# LeftHandPath.net
KiCad netlist of a schematic drawn in EAGLE
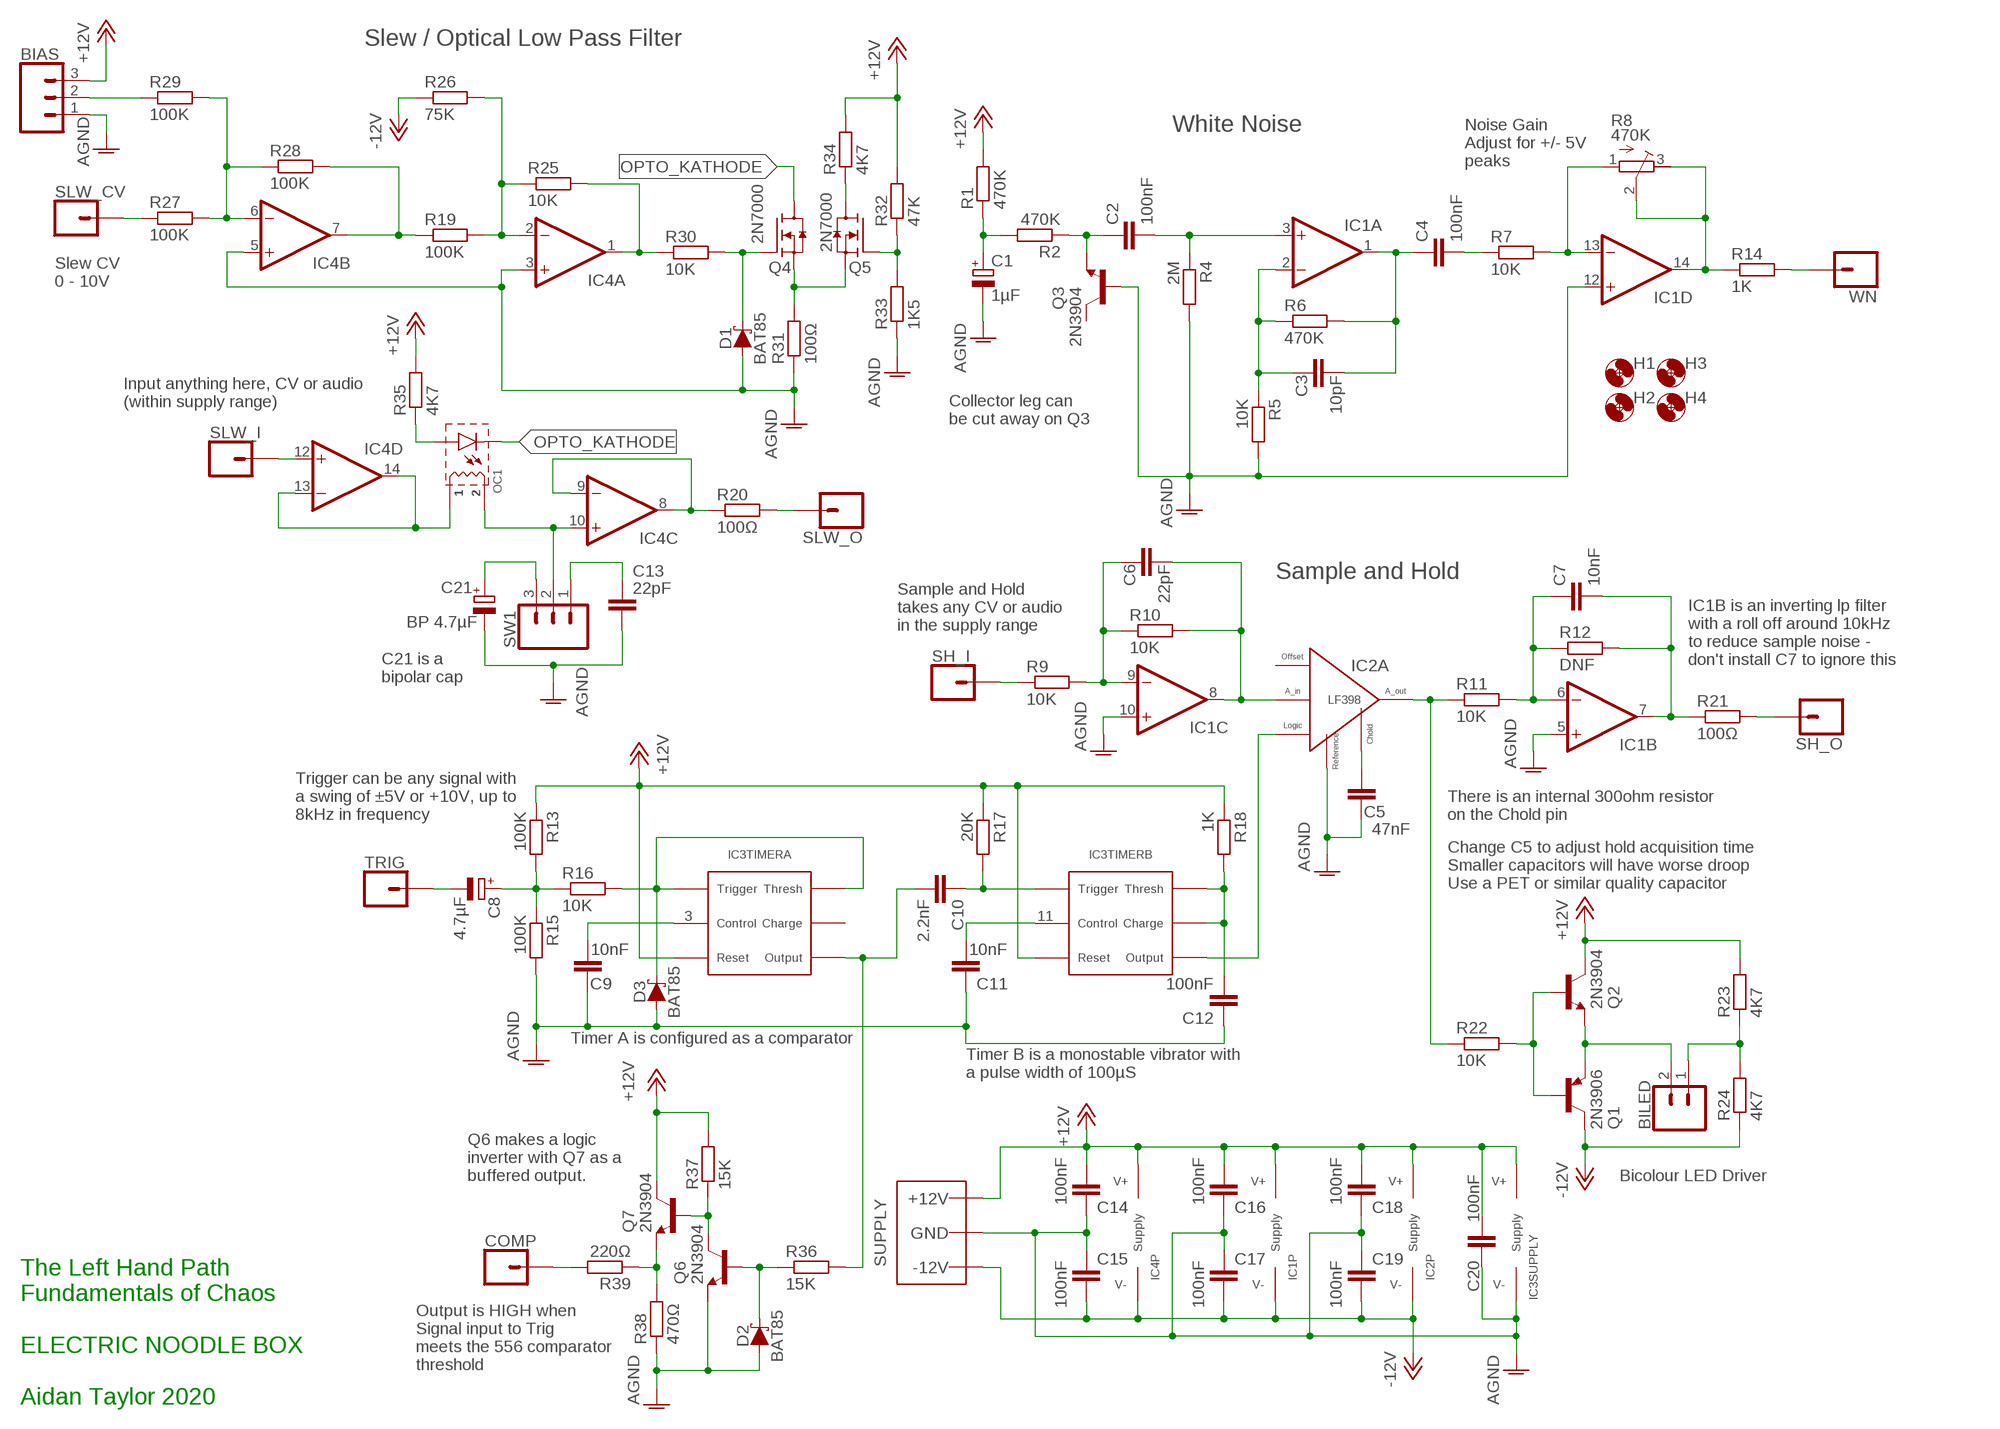
[diagram p0: schematic, sheet 1]

(export (version "E")
  (design (tool "Eeschema 10.0.6"))
  (components
    (comp (ref "BIAS")
      (value "3XWIREPAD")
      (footprint "eagle-import:1X03")
      (libsource (lib "eagle-import") (part "3XWIREPAD"))
    )
    (comp (ref "BILED")
      (value "2XWIREPAD")
      (footprint "eagle-import:1X02")
      (libsource (lib "eagle-import") (part "2XWIREPAD"))
    )
    (comp (ref "C1")
      (value "1µF")
      (footprint "eagle-import:E2-5")
      (libsource (lib "eagle-import") (part "CPOL-EUE2-5"))
    )
    (comp (ref "C2")
      (value "100nF")
      (footprint "eagle-import:C050-025X075")
      (libsource (lib "eagle-import") (part "C-EU050-025X075"))
    )
    (comp (ref "C3")
      (value "10pF")
      (footprint "eagle-import:C050-025X075")
      (libsource (lib "eagle-import") (part "C-EU050-025X075"))
    )
    (comp (ref "C4")
      (value "100nF")
      (footprint "eagle-import:C050-025X075")
      (libsource (lib "eagle-import") (part "C-EU050-025X075"))
    )
    (comp (ref "C5")
      (value "47nF")
      (footprint "eagle-import:C050-025X075")
      (libsource (lib "eagle-import") (part "C-EU050-025X075"))
    )
    (comp (ref "C6")
      (value "22pF")
      (footprint "eagle-import:C050-025X075")
      (libsource (lib "eagle-import") (part "C-EU050-025X075"))
    )
    (comp (ref "C7")
      (value "10nF")
      (footprint "eagle-import:C050-025X075")
      (libsource (lib "eagle-import") (part "C-EU050-025X075"))
    )
    (comp (ref "C8")
      (value "4.7µF")
      (footprint "eagle-import:E2-5")
      (libsource (lib "eagle-import") (part "CPOL-EUE2-5"))
    )
    (comp (ref "C9")
      (value "10nF")
      (footprint "eagle-import:C050-025X075")
      (libsource (lib "eagle-import") (part "C-EU050-025X075"))
    )
    (comp (ref "C10")
      (value "2.2nF")
      (footprint "eagle-import:C050-025X075")
      (libsource (lib "eagle-import") (part "C-EU050-025X075"))
    )
    (comp (ref "C11")
      (value "10nF")
      (footprint "eagle-import:C050-025X075")
      (libsource (lib "eagle-import") (part "C-EU050-025X075"))
    )
    (comp (ref "C12")
      (value "100nF")
      (footprint "eagle-import:C050-025X075")
      (libsource (lib "eagle-import") (part "C-EU050-025X075"))
    )
    (comp (ref "C13")
      (value "22pF")
      (footprint "eagle-import:C050-025X075")
      (libsource (lib "eagle-import") (part "C-EU050-025X075"))
    )
    (comp (ref "C14")
      (value "100nF")
      (footprint "eagle-import:C050-025X075")
      (libsource (lib "eagle-import") (part "C-EU050-025X075"))
    )
    (comp (ref "C15")
      (value "100nF")
      (footprint "eagle-import:C050-025X075")
      (libsource (lib "eagle-import") (part "C-EU050-025X075"))
    )
    (comp (ref "C16")
      (value "100nF")
      (footprint "eagle-import:C050-025X075")
      (libsource (lib "eagle-import") (part "C-EU050-025X075"))
    )
    (comp (ref "C17")
      (value "100nF")
      (footprint "eagle-import:C050-025X075")
      (libsource (lib "eagle-import") (part "C-EU050-025X075"))
    )
    (comp (ref "C18")
      (value "100nF")
      (footprint "eagle-import:C050-025X075")
      (libsource (lib "eagle-import") (part "C-EU050-025X075"))
    )
    (comp (ref "C19")
      (value "100nF")
      (footprint "eagle-import:C050-025X075")
      (libsource (lib "eagle-import") (part "C-EU050-025X075"))
    )
    (comp (ref "C20")
      (value "100nF")
      (footprint "eagle-import:C050-025X075")
      (libsource (lib "eagle-import") (part "C-EU050-025X075"))
    )
    (comp (ref "C21")
      (value "BP 4.7µF")
      (footprint "eagle-import:E2-5")
      (libsource (lib "eagle-import") (part "CPOL-EUE2-5"))
    )
    (comp (ref "COMP")
      (value "1XWIREPAD")
      (footprint "eagle-import:1X01")
      (libsource (lib "eagle-import") (part "1XWIREPAD"))
    )
    (comp (ref "D1")
      (value "BAT85")
      (footprint "eagle-import:DO35-7")
      (libsource (lib "eagle-import") (part "SCHOTTKY_DO35"))
    )
    (comp (ref "D2")
      (value "BAT85")
      (footprint "eagle-import:DO35-7")
      (libsource (lib "eagle-import") (part "SCHOTTKY_DO35"))
    )
    (comp (ref "D3")
      (value "BAT85")
      (footprint "eagle-import:DO35-7")
      (libsource (lib "eagle-import") (part "SCHOTTKY_DO35"))
    )
    (comp (ref "H1")
      (value "MOUNT-HOLE3.2")
      (footprint "eagle-import:3,2")
      (libsource (lib "eagle-import") (part "MOUNT-HOLE3.2"))
    )
    (comp (ref "H2")
      (value "MOUNT-HOLE3.2")
      (footprint "eagle-import:3,2")
      (libsource (lib "eagle-import") (part "MOUNT-HOLE3.2"))
    )
    (comp (ref "H3")
      (value "MOUNT-HOLE3.2")
      (footprint "eagle-import:3,2")
      (libsource (lib "eagle-import") (part "MOUNT-HOLE3.2"))
    )
    (comp (ref "H4")
      (value "MOUNT-HOLE3.2")
      (footprint "eagle-import:3,2")
      (libsource (lib "eagle-import") (part "MOUNT-HOLE3.2"))
    )
    (comp (ref "IC1")
      (value "TL0X4DIL")
      (footprint "eagle-import:DIL14")
      (libsource (lib "eagle-import") (part "TL0X4DIL"))
    )
    (comp (ref "IC2")
      (value "LF398")
      (footprint "eagle-import:DIL08")
      (libsource (lib "eagle-import") (part "LF398"))
    )
    (comp (ref "IC3")
      (value "556_DUALTIMERDIL14")
      (footprint "eagle-import:DIL14")
      (libsource (lib "eagle-import") (part "556_DUALTIMERDIL14"))
    )
    (comp (ref "IC4")
      (value "TL0X4DIL")
      (footprint "eagle-import:DIL14")
      (libsource (lib "eagle-import") (part "TL0X4DIL"))
    )
    (comp (ref "OC1")
      (value "OPTOCOUPLERSILONEX")
      (footprint "eagle-import:SILONEX_OPTOCOUPLER")
      (libsource (lib "eagle-import") (part "OPTOCOUPLERSILONEX"))
    )
    (comp (ref "Q1")
      (value "2N3906")
      (footprint "eagle-import:TO92")
      (libsource (lib "eagle-import") (part "2N3906"))
    )
    (comp (ref "Q2")
      (value "2N3904")
      (footprint "eagle-import:TO92")
      (libsource (lib "eagle-import") (part "2N3904"))
    )
    (comp (ref "Q3")
      (value "2N3904")
      (footprint "eagle-import:TO92")
      (libsource (lib "eagle-import") (part "2N3904"))
    )
    (comp (ref "Q4")
      (value "2N7000")
      (footprint "eagle-import:TO92")
      (libsource (lib "eagle-import") (part "2N7000"))
    )
    (comp (ref "Q5")
      (value "2N7000")
      (footprint "eagle-import:TO92")
      (libsource (lib "eagle-import") (part "2N7000"))
    )
    (comp (ref "Q6")
      (value "2N3904")
      (footprint "eagle-import:TO92")
      (libsource (lib "eagle-import") (part "2N3904"))
    )
    (comp (ref "Q7")
      (value "2N3904")
      (footprint "eagle-import:TO92")
      (libsource (lib "eagle-import") (part "2N3904"))
    )
    (comp (ref "R1")
      (value "470K")
      (footprint "eagle-import:0207_7")
      (libsource (lib "eagle-import") (part "R-EU_0207/7"))
    )
    (comp (ref "R2")
      (value "470K")
      (footprint "eagle-import:0207_7")
      (libsource (lib "eagle-import") (part "R-EU_0207/7"))
    )
    (comp (ref "R4")
      (value "2M")
      (footprint "eagle-import:0207_7")
      (libsource (lib "eagle-import") (part "R-EU_0207/7"))
    )
    (comp (ref "R5")
      (value "10K")
      (footprint "eagle-import:0207_7")
      (libsource (lib "eagle-import") (part "R-EU_0207/7"))
    )
    (comp (ref "R6")
      (value "470K")
      (footprint "eagle-import:0207_7")
      (libsource (lib "eagle-import") (part "R-EU_0207/7"))
    )
    (comp (ref "R7")
      (value "10K")
      (footprint "eagle-import:0207_7")
      (libsource (lib "eagle-import") (part "R-EU_0207/7"))
    )
    (comp (ref "R8")
      (value "470K")
      (footprint "eagle-import:RTRIM3296W")
      (libsource (lib "eagle-import") (part "R-TRIMM3296W"))
    )
    (comp (ref "R9")
      (value "10K")
      (footprint "eagle-import:0207_7")
      (libsource (lib "eagle-import") (part "R-EU_0207/7"))
    )
    (comp (ref "R10")
      (value "10K")
      (footprint "eagle-import:0207_7")
      (libsource (lib "eagle-import") (part "R-EU_0207/7"))
    )
    (comp (ref "R11")
      (value "10K")
      (footprint "eagle-import:0207_7")
      (libsource (lib "eagle-import") (part "R-EU_0207/7"))
    )
    (comp (ref "R12")
      (value "DNF")
      (footprint "eagle-import:0207_7")
      (libsource (lib "eagle-import") (part "R-EU_0207/7"))
    )
    (comp (ref "R13")
      (value "100K")
      (footprint "eagle-import:0207_7")
      (libsource (lib "eagle-import") (part "R-EU_0207/7"))
    )
    (comp (ref "R14")
      (value "1K")
      (footprint "eagle-import:0207_7")
      (libsource (lib "eagle-import") (part "R-EU_0207/7"))
    )
    (comp (ref "R15")
      (value "100K")
      (footprint "eagle-import:0207_7")
      (libsource (lib "eagle-import") (part "R-EU_0207/7"))
    )
    (comp (ref "R16")
      (value "10K")
      (footprint "eagle-import:0207_7")
      (libsource (lib "eagle-import") (part "R-EU_0207/7"))
    )
    (comp (ref "R17")
      (value "20K")
      (footprint "eagle-import:0207_7")
      (libsource (lib "eagle-import") (part "R-EU_0207/7"))
    )
    (comp (ref "R18")
      (value "1K")
      (footprint "eagle-import:0207_7")
      (libsource (lib "eagle-import") (part "R-EU_0207/7"))
    )
    (comp (ref "R19")
      (value "100K")
      (footprint "eagle-import:0207_7")
      (libsource (lib "eagle-import") (part "R-EU_0207/7"))
    )
    (comp (ref "R20")
      (value "100Ω")
      (footprint "eagle-import:0207_7")
      (libsource (lib "eagle-import") (part "R-EU_0207/7"))
    )
    (comp (ref "R21")
      (value "100Ω")
      (footprint "eagle-import:0207_7")
      (libsource (lib "eagle-import") (part "R-EU_0207/7"))
    )
    (comp (ref "R22")
      (value "10K")
      (footprint "eagle-import:0207_7")
      (libsource (lib "eagle-import") (part "R-EU_0207/7"))
    )
    (comp (ref "R23")
      (value "4K7")
      (footprint "eagle-import:0207_7")
      (libsource (lib "eagle-import") (part "R-EU_0207/7"))
    )
    (comp (ref "R24")
      (value "4K7")
      (footprint "eagle-import:0207_7")
      (libsource (lib "eagle-import") (part "R-EU_0207/7"))
    )
    (comp (ref "R25")
      (value "10K")
      (footprint "eagle-import:0207_7")
      (libsource (lib "eagle-import") (part "R-EU_0207/7"))
    )
    (comp (ref "R26")
      (value "75K")
      (footprint "eagle-import:0207_7")
      (libsource (lib "eagle-import") (part "R-EU_0207/7"))
    )
    (comp (ref "R27")
      (value "100K")
      (footprint "eagle-import:0207_7")
      (libsource (lib "eagle-import") (part "R-EU_0207/7"))
    )
    (comp (ref "R28")
      (value "100K")
      (footprint "eagle-import:0207_7")
      (libsource (lib "eagle-import") (part "R-EU_0207/7"))
    )
    (comp (ref "R29")
      (value "100K")
      (footprint "eagle-import:0207_7")
      (libsource (lib "eagle-import") (part "R-EU_0207/7"))
    )
    (comp (ref "R30")
      (value "10K")
      (footprint "eagle-import:0207_7")
      (libsource (lib "eagle-import") (part "R-EU_0207/7"))
    )
    (comp (ref "R31")
      (value "100Ω")
      (footprint "eagle-import:0207_7")
      (libsource (lib "eagle-import") (part "R-EU_0207/7"))
    )
    (comp (ref "R32")
      (value "47K")
      (footprint "eagle-import:0207_7")
      (libsource (lib "eagle-import") (part "R-EU_0207/7"))
    )
    (comp (ref "R33")
      (value "1K5")
      (footprint "eagle-import:0207_7")
      (libsource (lib "eagle-import") (part "R-EU_0207/7"))
    )
    (comp (ref "R34")
      (value "4K7")
      (footprint "eagle-import:0207_7")
      (libsource (lib "eagle-import") (part "R-EU_0207/7"))
    )
    (comp (ref "R35")
      (value "4K7")
      (footprint "eagle-import:0207_7")
      (libsource (lib "eagle-import") (part "R-EU_0207/7"))
    )
    (comp (ref "R36")
      (value "15K")
      (footprint "eagle-import:0207_7")
      (libsource (lib "eagle-import") (part "R-EU_0207/7"))
    )
    (comp (ref "R37")
      (value "15K")
      (footprint "eagle-import:0207_7")
      (libsource (lib "eagle-import") (part "R-EU_0207/7"))
    )
    (comp (ref "R38")
      (value "470Ω")
      (footprint "eagle-import:0207_7")
      (libsource (lib "eagle-import") (part "R-EU_0207/7"))
    )
    (comp (ref "R39")
      (value "220Ω")
      (footprint "eagle-import:0207_7")
      (libsource (lib "eagle-import") (part "R-EU_0207/7"))
    )
    (comp (ref "SH_I")
      (value "1XWIREPAD")
      (footprint "eagle-import:1X01")
      (libsource (lib "eagle-import") (part "1XWIREPAD"))
    )
    (comp (ref "SH_O")
      (value "1XWIREPAD")
      (footprint "eagle-import:1X01")
      (libsource (lib "eagle-import") (part "1XWIREPAD"))
    )
    (comp (ref "SLW_CV")
      (value "1XWIREPAD")
      (footprint "eagle-import:1X01")
      (libsource (lib "eagle-import") (part "1XWIREPAD"))
    )
    (comp (ref "SLW_I")
      (value "1XWIREPAD")
      (footprint "eagle-import:1X01")
      (libsource (lib "eagle-import") (part "1XWIREPAD"))
    )
    (comp (ref "SLW_O")
      (value "1XWIREPAD")
      (footprint "eagle-import:1X01")
      (libsource (lib "eagle-import") (part "1XWIREPAD"))
    )
    (comp (ref "SW1")
      (value "3XWIREPAD")
      (footprint "eagle-import:1X03")
      (libsource (lib "eagle-import") (part "3XWIREPAD"))
    )
    (comp (ref "TRIG")
      (value "1XWIREPAD")
      (footprint "eagle-import:1X01")
      (libsource (lib "eagle-import") (part "1XWIREPAD"))
    )
    (comp (ref "WN")
      (value "1XWIREPAD")
      (footprint "eagle-import:1X01")
      (libsource (lib "eagle-import") (part "1XWIREPAD"))
    )
    (comp (ref "WP1")
      (value "COMBO_SUPPLY_HEADER")
      (footprint "eagle-import:COMBINED_POWER")
      (libsource (lib "eagle-import") (part "COMBO_SUPPLY_HEADER"))
    )
  )
  (nets
    (net (code "1") (name "+12V") (class "Default")
      (node (ref "BIAS") (pin "3") (pinfunction "3_3") (pintype "passive"))
      (node (ref "C14") (pin "2") (pinfunction "2_2") (pintype "passive"))
      (node (ref "C16") (pin "2") (pinfunction "2_2") (pintype "passive"))
      (node (ref "C18") (pin "2") (pinfunction "2_2") (pintype "passive"))
      (node (ref "C20") (pin "2") (pinfunction "2_2") (pintype "passive"))
      (node (ref "IC1") (pin "4") (pinfunction "V+_4") (pintype "bidirectional"))
      (node (ref "IC2") (pin "1") (pinfunction "V+_1") (pintype "bidirectional"))
      (node (ref "IC3") (pin "10") (pinfunction "RESET_10") (pintype "bidirectional"))
      (node (ref "IC3") (pin "14") (pinfunction "V+_14") (pintype "bidirectional"))
      (node (ref "IC3") (pin "4") (pinfunction "RESET_4") (pintype "bidirectional"))
      (node (ref "IC4") (pin "4") (pinfunction "V+_4") (pintype "bidirectional"))
      (node (ref "Q2") (pin "1") (pinfunction "C_1") (pintype "passive"))
      (node (ref "Q7") (pin "1") (pinfunction "C_1") (pintype "passive"))
      (node (ref "R1") (pin "2") (pinfunction "2_2") (pintype "passive"))
      (node (ref "R13") (pin "1") (pinfunction "1_1") (pintype "passive"))
      (node (ref "R17") (pin "1") (pinfunction "1_1") (pintype "passive"))
      (node (ref "R18") (pin "1") (pinfunction "1_1") (pintype "passive"))
      (node (ref "R23") (pin "2") (pinfunction "2_2") (pintype "passive"))
      (node (ref "R32") (pin "2") (pinfunction "2_2") (pintype "passive"))
      (node (ref "R34") (pin "2") (pinfunction "2_2") (pintype "passive"))
      (node (ref "R35") (pin "2") (pinfunction "2_2") (pintype "passive"))
      (node (ref "R37") (pin "2") (pinfunction "2_2") (pintype "passive"))
      (node (ref "WP1") (pin "V+1") (pinfunction "V++_V+1") (pintype "power_in"))
      (node (ref "WP1") (pin "V+2") (pinfunction "V++_V+2") (pintype "power_in"))
      (node (ref "WP1") (pin "V+3") (pinfunction "V++_V+3") (pintype "power_in"))
    )
    (net (code "2") (name "-12V") (class "Default")
      (node (ref "C15") (pin "1") (pinfunction "1_1") (pintype "passive"))
      (node (ref "C17") (pin "1") (pinfunction "1_1") (pintype "passive"))
      (node (ref "C19") (pin "1") (pinfunction "1_1") (pintype "passive"))
      (node (ref "IC1") (pin "11") (pinfunction "V-_11") (pintype "bidirectional"))
      (node (ref "IC2") (pin "4") (pinfunction "V-_4") (pintype "bidirectional"))
      (node (ref "IC4") (pin "11") (pinfunction "V-_11") (pintype "bidirectional"))
      (node (ref "Q1") (pin "1") (pinfunction "C_1") (pintype "passive"))
      (node (ref "R24") (pin "1") (pinfunction "1_1") (pintype "passive"))
      (node (ref "R26") (pin "1") (pinfunction "1_1") (pintype "passive"))
      (node (ref "WP1") (pin "V-1") (pinfunction "V--_V-1") (pintype "power_in"))
      (node (ref "WP1") (pin "V-2") (pinfunction "V--_V-2") (pintype "power_in"))
      (node (ref "WP1") (pin "V-3") (pinfunction "V--_V-3") (pintype "power_in"))
    )
    (net (code "3") (name "AGND") (class "Default")
      (node (ref "BIAS") (pin "1") (pinfunction "1_1") (pintype "passive"))
      (node (ref "C1") (pin "-") (pinfunction "-_-") (pintype "passive"))
      (node (ref "C11") (pin "1") (pinfunction "1_1") (pintype "passive"))
      (node (ref "C12") (pin "1") (pinfunction "1_1") (pintype "passive"))
      (node (ref "C13") (pin "1") (pinfunction "1_1") (pintype "passive"))
      (node (ref "C14") (pin "1") (pinfunction "1_1") (pintype "passive"))
      (node (ref "C15") (pin "2") (pinfunction "2_2") (pintype "passive"))
      (node (ref "C16") (pin "1") (pinfunction "1_1") (pintype "passive"))
      (node (ref "C17") (pin "2") (pinfunction "2_2") (pintype "passive"))
      (node (ref "C18") (pin "1") (pinfunction "1_1") (pintype "passive"))
      (node (ref "C19") (pin "2") (pinfunction "2_2") (pintype "passive"))
      (node (ref "C20") (pin "1") (pinfunction "1_1") (pintype "passive"))
      (node (ref "C21") (pin "-") (pinfunction "-_-") (pintype "passive"))
      (node (ref "C5") (pin "1") (pinfunction "1_1") (pintype "passive"))
      (node (ref "C9") (pin "1") (pinfunction "1_1") (pintype "passive"))
      (node (ref "D1") (pin "A") (pinfunction "A_A") (pintype "passive"))
      (node (ref "D2") (pin "A") (pinfunction "A_A") (pintype "passive"))
      (node (ref "D3") (pin "A") (pinfunction "A_A") (pintype "passive"))
      (node (ref "IC1") (pin "10") (pinfunction "+IN_10") (pintype "input"))
      (node (ref "IC1") (pin "12") (pinfunction "+IN_12") (pintype "input"))
      (node (ref "IC1") (pin "5") (pinfunction "+IN_5") (pintype "input"))
      (node (ref "IC2") (pin "7") (pinfunction "REFERENCE_7") (pintype "input"))
      (node (ref "IC3") (pin "7") (pinfunction "V-_7") (pintype "bidirectional"))
      (node (ref "IC4") (pin "3") (pinfunction "+IN_3") (pintype "input"))
      (node (ref "IC4") (pin "5") (pinfunction "+IN_5") (pintype "input"))
      (node (ref "Q3") (pin "2") (pinfunction "B_2") (pintype "passive"))
      (node (ref "Q6") (pin "3") (pinfunction "E_3") (pintype "passive"))
      (node (ref "R15") (pin "2") (pinfunction "2_2") (pintype "passive"))
      (node (ref "R31") (pin "1") (pinfunction "1_1") (pintype "passive"))
      (node (ref "R33") (pin "1") (pinfunction "1_1") (pintype "passive"))
      (node (ref "R38") (pin "1") (pinfunction "1_1") (pintype "passive"))
      (node (ref "R4") (pin "2") (pinfunction "2_2") (pintype "passive"))
      (node (ref "R5") (pin "2") (pinfunction "2_2") (pintype "passive"))
      (node (ref "WP1") (pin "GND1") (pinfunction "AGND_GND1") (pintype "power_in"))
      (node (ref "WP1") (pin "GND2") (pinfunction "AGND_GND2") (pintype "power_in"))
      (node (ref "WP1") (pin "GND3") (pinfunction "AGND_GND3") (pintype "power_in"))
      (node (ref "WP1") (pin "GND4") (pinfunction "AGND_GND4") (pintype "power_in"))
      (node (ref "WP1") (pin "GND5") (pinfunction "AGND_GND5") (pintype "power_in"))
      (node (ref "WP1") (pin "GND6") (pinfunction "AGND_GND6") (pintype "power_in"))
      (node (ref "WP1") (pin "GND7") (pinfunction "AGND_GND7") (pintype "power_in"))
      (node (ref "WP1") (pin "GND8") (pinfunction "AGND_GND8") (pintype "power_in"))
    )
    (net (code "4") (name "Net-(BIAS-Pad2)") (class "Default")
      (node (ref "BIAS") (pin "2") (pinfunction "2_2") (pintype "passive"))
      (node (ref "R29") (pin "1") (pinfunction "1_1") (pintype "passive"))
    )
    (net (code "5") (name "Net-(BILED-Pad1)") (class "Default")
      (node (ref "BILED") (pin "1") (pinfunction "1_1") (pintype "passive"))
      (node (ref "R23") (pin "1") (pinfunction "1_1") (pintype "passive"))
      (node (ref "R24") (pin "2") (pinfunction "2_2") (pintype "passive"))
    )
    (net (code "6") (name "Net-(C1-Pad+)") (class "Default")
      (node (ref "C1") (pin "+") (pinfunction "+_+") (pintype "passive"))
      (node (ref "R1") (pin "1") (pinfunction "1_1") (pintype "passive"))
      (node (ref "R2") (pin "2") (pinfunction "2_2") (pintype "passive"))
    )
    (net (code "7") (name "Net-(C4-Pad2)") (class "Default")
      (node (ref "C4") (pin "2") (pinfunction "2_2") (pintype "passive"))
      (node (ref "R7") (pin "1") (pinfunction "1_1") (pintype "passive"))
    )
    (net (code "8") (name "Net-(C8-Pad+)") (class "Default")
      (node (ref "C8") (pin "+") (pinfunction "+_+") (pintype "passive"))
      (node (ref "R13") (pin "2") (pinfunction "2_2") (pintype "passive"))
      (node (ref "R15") (pin "1") (pinfunction "1_1") (pintype "passive"))
      (node (ref "R16") (pin "1") (pinfunction "1_1") (pintype "passive"))
    )
    (net (code "9") (name "Net-(C8-Pad-)") (class "Default")
      (node (ref "C8") (pin "-") (pinfunction "-_-") (pintype "passive"))
      (node (ref "TRIG") (pin "1") (pinfunction "1_1") (pintype "passive"))
    )
    (net (code "10") (name "Net-(C13-Pad2)") (class "Default")
      (node (ref "C13") (pin "2") (pinfunction "2_2") (pintype "passive"))
      (node (ref "SW1") (pin "1") (pinfunction "1_1") (pintype "passive"))
    )
    (net (code "11") (name "Net-(C21-Pad+)") (class "Default")
      (node (ref "C21") (pin "+") (pinfunction "+_+") (pintype "passive"))
      (node (ref "SW1") (pin "3") (pinfunction "3_3") (pintype "passive"))
    )
    (net (code "12") (name "Net-(COMP-Pad1)") (class "Default")
      (node (ref "COMP") (pin "1") (pinfunction "1_1") (pintype "passive"))
      (node (ref "R39") (pin "2") (pinfunction "2_2") (pintype "passive"))
    )
    (net (code "13") (name "Net-(IC1A-+IN)") (class "Default")
      (node (ref "C2") (pin "2") (pinfunction "2_2") (pintype "passive"))
      (node (ref "IC1") (pin "3") (pinfunction "+IN_3") (pintype "input"))
      (node (ref "R4") (pin "1") (pinfunction "1_1") (pintype "passive"))
    )
    (net (code "14") (name "Net-(IC1A--IN)") (class "Default")
      (node (ref "C3") (pin "1") (pinfunction "1_1") (pintype "passive"))
      (node (ref "IC1") (pin "2") (pinfunction "-IN_2") (pintype "input"))
      (node (ref "R5") (pin "1") (pinfunction "1_1") (pintype "passive"))
      (node (ref "R6") (pin "1") (pinfunction "1_1") (pintype "passive"))
    )
    (net (code "15") (name "Net-(IC1A-OUT)") (class "Default")
      (node (ref "C3") (pin "2") (pinfunction "2_2") (pintype "passive"))
      (node (ref "C4") (pin "1") (pinfunction "1_1") (pintype "passive"))
      (node (ref "IC1") (pin "1") (pinfunction "OUT_1") (pintype "output"))
      (node (ref "R6") (pin "2") (pinfunction "2_2") (pintype "passive"))
    )
    (net (code "16") (name "Net-(IC1B--IN)") (class "Default")
      (node (ref "C7") (pin "1") (pinfunction "1_1") (pintype "passive"))
      (node (ref "IC1") (pin "6") (pinfunction "-IN_6") (pintype "input"))
      (node (ref "R11") (pin "2") (pinfunction "2_2") (pintype "passive"))
      (node (ref "R12") (pin "1") (pinfunction "1_1") (pintype "passive"))
    )
    (net (code "17") (name "Net-(IC1B-OUT)") (class "Default")
      (node (ref "C7") (pin "2") (pinfunction "2_2") (pintype "passive"))
      (node (ref "IC1") (pin "7") (pinfunction "OUT_7") (pintype "output"))
      (node (ref "R12") (pin "2") (pinfunction "2_2") (pintype "passive"))
      (node (ref "R21") (pin "1") (pinfunction "1_1") (pintype "passive"))
    )
    (net (code "18") (name "Net-(IC1C--IN)") (class "Default")
      (node (ref "C6") (pin "1") (pinfunction "1_1") (pintype "passive"))
      (node (ref "IC1") (pin "9") (pinfunction "-IN_9") (pintype "input"))
      (node (ref "R10") (pin "1") (pinfunction "1_1") (pintype "passive"))
      (node (ref "R9") (pin "2") (pinfunction "2_2") (pintype "passive"))
    )
    (net (code "19") (name "Net-(IC1C-OUT)") (class "Default")
      (node (ref "C6") (pin "2") (pinfunction "2_2") (pintype "passive"))
      (node (ref "IC1") (pin "8") (pinfunction "OUT_8") (pintype "output"))
      (node (ref "IC2") (pin "3") (pinfunction "ANALOG_IN_3") (pintype "input"))
      (node (ref "R10") (pin "2") (pinfunction "2_2") (pintype "passive"))
    )
    (net (code "20") (name "Net-(IC1D--IN)") (class "Default")
      (node (ref "IC1") (pin "13") (pinfunction "-IN_13") (pintype "input"))
      (node (ref "R7") (pin "2") (pinfunction "2_2") (pintype "passive"))
      (node (ref "R8") (pin "1") (pinfunction "A_1") (pintype "passive"))
    )
    (net (code "21") (name "Net-(IC1D-OUT)") (class "Default")
      (node (ref "IC1") (pin "14") (pinfunction "OUT_14") (pintype "output"))
      (node (ref "R14") (pin "1") (pinfunction "1_1") (pintype "passive"))
      (node (ref "R8") (pin "2") (pinfunction "S_2") (pintype "passive"))
      (node (ref "R8") (pin "3") (pinfunction "E_3") (pintype "passive"))
    )
    (net (code "22") (name "Net-(IC2A-ANALOG_OUT)") (class "Default")
      (node (ref "IC2") (pin "5") (pinfunction "ANALOG_OUT_5") (pintype "output"))
      (node (ref "R11") (pin "1") (pinfunction "1_1") (pintype "passive"))
      (node (ref "R22") (pin "1") (pinfunction "1_1") (pintype "passive"))
    )
    (net (code "23") (name "Net-(IC2A-CH)") (class "Default")
      (node (ref "C5") (pin "2") (pinfunction "2_2") (pintype "passive"))
      (node (ref "IC2") (pin "6") (pinfunction "CH_6") (pintype "input"))
    )
    (net (code "24") (name "Net-(IC2A-LOGIC)") (class "Default")
      (node (ref "IC2") (pin "8") (pinfunction "LOGIC_8") (pintype "input"))
      (node (ref "IC3") (pin "9") (pinfunction "OUTPUT_9") (pintype "bidirectional"))
    )
    (net (code "25") (name "Net-(IC3B-CONT)") (class "Default")
      (node (ref "C9") (pin "2") (pinfunction "2_2") (pintype "passive"))
      (node (ref "IC3") (pin "3") (pinfunction "CONT_3") (pintype "bidirectional"))
    )
    (net (code "26") (name "Net-(IC3B-OUTPUT)") (class "Default")
      (node (ref "C10") (pin "2") (pinfunction "2_2") (pintype "passive"))
      (node (ref "IC3") (pin "5") (pinfunction "OUTPUT_5") (pintype "bidirectional"))
      (node (ref "R36") (pin "2") (pinfunction "2_2") (pintype "passive"))
    )
    (net (code "27") (name "Net-(IC3B-THRESHOLD)") (class "Default")
      (node (ref "D3") (pin "C") (pinfunction "C_C") (pintype "passive"))
      (node (ref "IC3") (pin "2") (pinfunction "THRESHOLD_2") (pintype "bidirectional"))
      (node (ref "IC3") (pin "6") (pinfunction "TRIGGER_6") (pintype "bidirectional"))
      (node (ref "R16") (pin "2") (pinfunction "2_2") (pintype "passive"))
    )
    (net (code "28") (name "Net-(IC3C-CONT)") (class "Default")
      (node (ref "C11") (pin "2") (pinfunction "2_2") (pintype "passive"))
      (node (ref "IC3") (pin "11") (pinfunction "CONT_11") (pintype "bidirectional"))
    )
    (net (code "29") (name "Net-(IC3C-DISCHARGE)") (class "Default")
      (node (ref "C12") (pin "2") (pinfunction "2_2") (pintype "passive"))
      (node (ref "IC3") (pin "12") (pinfunction "THRESHOLD_12") (pintype "bidirectional"))
      (node (ref "IC3") (pin "13") (pinfunction "DISCHARGE_13") (pintype "bidirectional"))
      (node (ref "R18") (pin "2") (pinfunction "2_2") (pintype "passive"))
    )
    (net (code "30") (name "Net-(IC3C-TRIGGER)") (class "Default")
      (node (ref "C10") (pin "1") (pinfunction "1_1") (pintype "passive"))
      (node (ref "IC3") (pin "8") (pinfunction "TRIGGER_8") (pintype "bidirectional"))
      (node (ref "R17") (pin "2") (pinfunction "2_2") (pintype "passive"))
    )
    (net (code "31") (name "Net-(IC4A--IN)") (class "Default")
      (node (ref "IC4") (pin "2") (pinfunction "-IN_2") (pintype "input"))
      (node (ref "R19") (pin "2") (pinfunction "2_2") (pintype "passive"))
      (node (ref "R25") (pin "1") (pinfunction "1_1") (pintype "passive"))
      (node (ref "R26") (pin "2") (pinfunction "2_2") (pintype "passive"))
    )
    (net (code "32") (name "Net-(IC4A-OUT)") (class "Default")
      (node (ref "IC4") (pin "1") (pinfunction "OUT_1") (pintype "output"))
      (node (ref "R25") (pin "2") (pinfunction "2_2") (pintype "passive"))
      (node (ref "R30") (pin "1") (pinfunction "1_1") (pintype "passive"))
    )
    (net (code "33") (name "Net-(IC4B--IN)") (class "Default")
      (node (ref "IC4") (pin "6") (pinfunction "-IN_6") (pintype "input"))
      (node (ref "R27") (pin "2") (pinfunction "2_2") (pintype "passive"))
      (node (ref "R28") (pin "1") (pinfunction "1_1") (pintype "passive"))
      (node (ref "R29") (pin "2") (pinfunction "2_2") (pintype "passive"))
    )
    (net (code "34") (name "Net-(IC4B-OUT)") (class "Default")
      (node (ref "IC4") (pin "7") (pinfunction "OUT_7") (pintype "output"))
      (node (ref "R19") (pin "1") (pinfunction "1_1") (pintype "passive"))
      (node (ref "R28") (pin "2") (pinfunction "2_2") (pintype "passive"))
    )
    (net (code "35") (name "Net-(IC4C-+IN)") (class "Default")
      (node (ref "IC4") (pin "10") (pinfunction "+IN_10") (pintype "input"))
      (node (ref "OC1") (pin "2") (pinfunction "R2_2") (pintype "bidirectional"))
      (node (ref "SW1") (pin "2") (pinfunction "2_2") (pintype "passive"))
    )
    (net (code "36") (name "Net-(IC4C--IN)") (class "Default")
      (node (ref "IC4") (pin "8") (pinfunction "OUT_8") (pintype "output"))
      (node (ref "IC4") (pin "9") (pinfunction "-IN_9") (pintype "input"))
      (node (ref "R20") (pin "1") (pinfunction "1_1") (pintype "passive"))
    )
    (net (code "37") (name "Net-(IC4D-+IN)") (class "Default")
      (node (ref "IC4") (pin "12") (pinfunction "+IN_12") (pintype "input"))
      (node (ref "SLW_I") (pin "1") (pinfunction "1_1") (pintype "passive"))
    )
    (net (code "38") (name "Net-(IC4D--IN)") (class "Default")
      (node (ref "IC4") (pin "13") (pinfunction "-IN_13") (pintype "input"))
      (node (ref "IC4") (pin "14") (pinfunction "OUT_14") (pintype "output"))
      (node (ref "OC1") (pin "1") (pinfunction "R1_1") (pintype "bidirectional"))
    )
    (net (code "39") (name "Net-(OC1-PadA)") (class "Default")
      (node (ref "OC1") (pin "A") (pinfunction "A_A") (pintype "passive"))
      (node (ref "R35") (pin "1") (pinfunction "1_1") (pintype "passive"))
    )
    (net (code "40") (name "Net-(Q1-B)") (class "Default")
      (node (ref "Q1") (pin "2") (pinfunction "B_2") (pintype "passive"))
      (node (ref "Q2") (pin "2") (pinfunction "B_2") (pintype "passive"))
      (node (ref "R22") (pin "2") (pinfunction "2_2") (pintype "passive"))
    )
    (net (code "41") (name "Net-(Q1-E)") (class "Default")
      (node (ref "BILED") (pin "2") (pinfunction "2_2") (pintype "passive"))
      (node (ref "Q1") (pin "3") (pinfunction "E_3") (pintype "passive"))
      (node (ref "Q2") (pin "3") (pinfunction "E_3") (pintype "passive"))
    )
    (net (code "42") (name "Net-(Q3-E)") (class "Default")
      (node (ref "C2") (pin "1") (pinfunction "1_1") (pintype "passive"))
      (node (ref "Q3") (pin "3") (pinfunction "E_3") (pintype "passive"))
      (node (ref "R2") (pin "1") (pinfunction "1_1") (pintype "passive"))
    )
    (net (code "43") (name "Net-(Q4-G)") (class "Default")
      (node (ref "D1") (pin "C") (pinfunction "C_C") (pintype "passive"))
      (node (ref "Q4") (pin "2") (pinfunction "G_2") (pintype "passive"))
      (node (ref "R30") (pin "2") (pinfunction "2_2") (pintype "passive"))
    )
    (net (code "44") (name "Net-(Q4-S)") (class "Default")
      (node (ref "Q4") (pin "1") (pinfunction "S_1") (pintype "passive"))
      (node (ref "Q5") (pin "1") (pinfunction "S_1") (pintype "passive"))
      (node (ref "R31") (pin "2") (pinfunction "2_2") (pintype "passive"))
    )
    (net (code "45") (name "Net-(Q5-D)") (class "Default")
      (node (ref "Q5") (pin "3") (pinfunction "D_3") (pintype "passive"))
      (node (ref "R34") (pin "1") (pinfunction "1_1") (pintype "passive"))
    )
    (net (code "46") (name "Net-(Q5-G)") (class "Default")
      (node (ref "Q5") (pin "2") (pinfunction "G_2") (pintype "passive"))
      (node (ref "R32") (pin "1") (pinfunction "1_1") (pintype "passive"))
      (node (ref "R33") (pin "2") (pinfunction "2_2") (pintype "passive"))
    )
    (net (code "47") (name "Net-(Q6-B)") (class "Default")
      (node (ref "D2") (pin "C") (pinfunction "C_C") (pintype "passive"))
      (node (ref "Q6") (pin "2") (pinfunction "B_2") (pintype "passive"))
      (node (ref "R36") (pin "1") (pinfunction "1_1") (pintype "passive"))
    )
    (net (code "48") (name "Net-(Q6-C)") (class "Default")
      (node (ref "Q6") (pin "1") (pinfunction "C_1") (pintype "passive"))
      (node (ref "Q7") (pin "2") (pinfunction "B_2") (pintype "passive"))
      (node (ref "R37") (pin "1") (pinfunction "1_1") (pintype "passive"))
    )
    (net (code "49") (name "Net-(Q7-E)") (class "Default")
      (node (ref "Q7") (pin "3") (pinfunction "E_3") (pintype "passive"))
      (node (ref "R38") (pin "2") (pinfunction "2_2") (pintype "passive"))
      (node (ref "R39") (pin "1") (pinfunction "1_1") (pintype "passive"))
    )
    (net (code "50") (name "Net-(R9-Pad1)") (class "Default")
      (node (ref "R9") (pin "1") (pinfunction "1_1") (pintype "passive"))
      (node (ref "SH_I") (pin "1") (pinfunction "1_1") (pintype "passive"))
    )
    (net (code "51") (name "Net-(R14-Pad2)") (class "Default")
      (node (ref "R14") (pin "2") (pinfunction "2_2") (pintype "passive"))
      (node (ref "WN") (pin "1") (pinfunction "1_1") (pintype "passive"))
    )
    (net (code "52") (name "Net-(R20-Pad2)") (class "Default")
      (node (ref "R20") (pin "2") (pinfunction "2_2") (pintype "passive"))
      (node (ref "SLW_O") (pin "1") (pinfunction "1_1") (pintype "passive"))
    )
    (net (code "53") (name "Net-(R21-Pad2)") (class "Default")
      (node (ref "R21") (pin "2") (pinfunction "2_2") (pintype "passive"))
      (node (ref "SH_O") (pin "1") (pinfunction "1_1") (pintype "passive"))
    )
    (net (code "54") (name "Net-(R27-Pad1)") (class "Default")
      (node (ref "R27") (pin "1") (pinfunction "1_1") (pintype "passive"))
      (node (ref "SLW_CV") (pin "1") (pinfunction "1_1") (pintype "passive"))
    )
    (net (code "55") (name "OPTO_KATHODE") (class "Default")
      (node (ref "OC1") (pin "K") (pinfunction "K_K") (pintype "passive"))
      (node (ref "Q4") (pin "3") (pinfunction "D_3") (pintype "passive"))
    )
    (net (code "56") (name "unconnected-(IC2A-OFFSET-Pad2)") (class "Default")
      (node (ref "IC2") (pin "2") (pinfunction "OFFSET_2") (pintype "input"))
    )
    (net (code "57") (name "unconnected-(IC3B-DISCHARGE-Pad1)") (class "Default")
      (node (ref "IC3") (pin "1") (pinfunction "DISCHARGE_1") (pintype "bidirectional"))
    )
    (net (code "58") (name "unconnected-(Q3-C-Pad1)") (class "Default")
      (node (ref "Q3") (pin "1") (pinfunction "C_1") (pintype "passive"))
    )
  )
)
